# team_flag.net
KiCad netlist of a schematic drawn in EAGLE
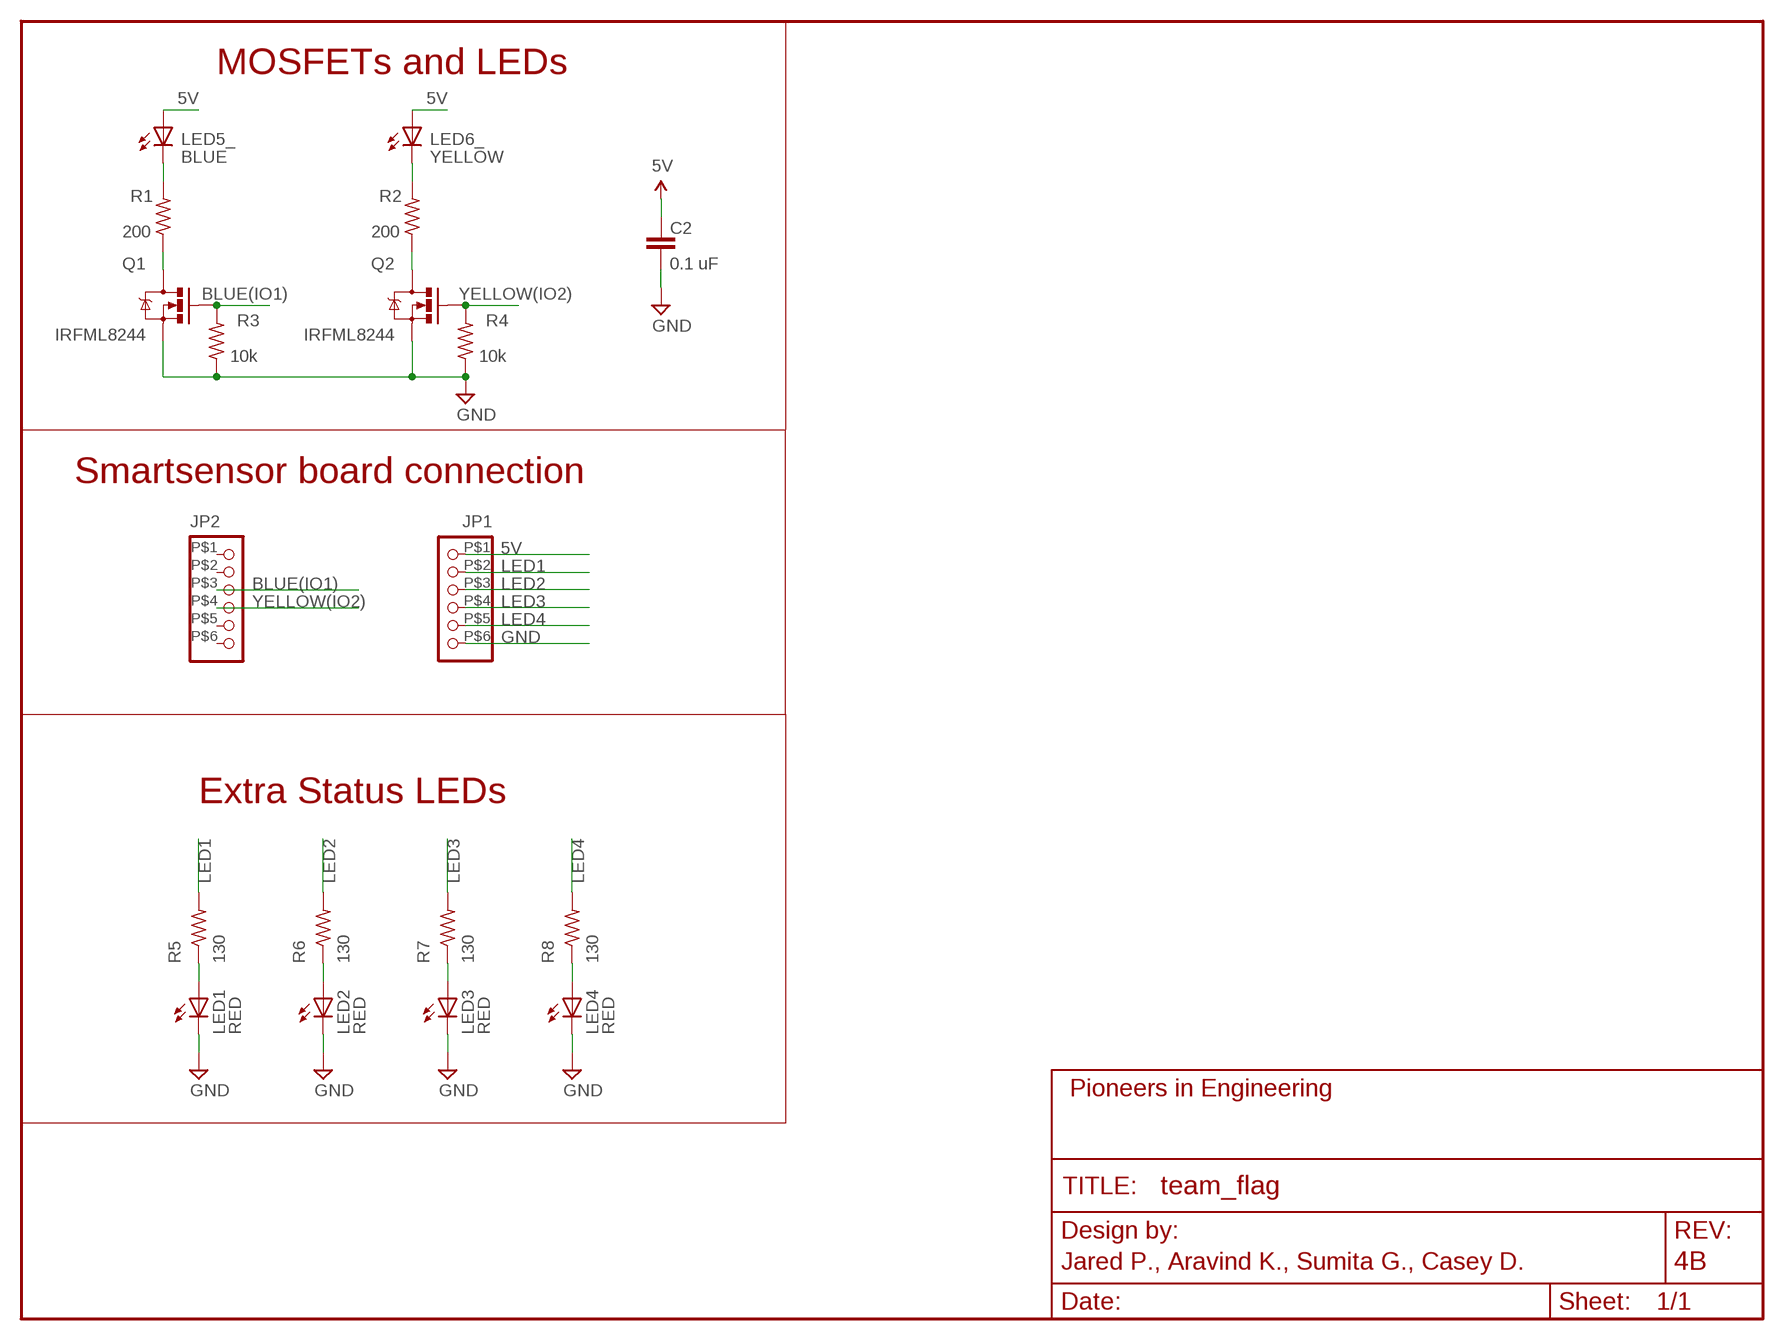
[diagram p0: schematic, sheet 1]

(export (version "E")
  (design (tool "Eeschema 10.0.6"))
  (components
    (comp (ref "C2")
      (value "0.1 uF")
      (footprint "eagle-import:0603-CAP")
      (libsource (lib "eagle-import") (part "CAP0603-CAP"))
    )
    (comp (ref "JP1")
      (value "PINHD-1X6SMD-C")
      (footprint "eagle-import:1X06-SMD-C")
      (libsource (lib "eagle-import") (part "PINHD-1X6SMD-C"))
    )
    (comp (ref "JP2")
      (value "PINHD-1X6SMD-C")
      (footprint "eagle-import:1X06-SMD-C")
      (libsource (lib "eagle-import") (part "PINHD-1X6SMD-C"))
    )
    (comp (ref "LED1")
      (value "RED")
      (footprint "eagle-import:LED-0805")
      (libsource (lib "eagle-import") (part "LED0805"))
    )
    (comp (ref "LED2")
      (value "RED")
      (footprint "eagle-import:LED-0805")
      (libsource (lib "eagle-import") (part "LED0805"))
    )
    (comp (ref "LED3")
      (value "RED")
      (footprint "eagle-import:LED-0805")
      (libsource (lib "eagle-import") (part "LED0805"))
    )
    (comp (ref "LED4")
      (value "RED")
      (footprint "eagle-import:LED-0805")
      (libsource (lib "eagle-import") (part "LED0805"))
    )
    (comp (ref "LED5_")
      (value "BLUE")
      (footprint "eagle-import:LED5MM-NOFLAT")
      (libsource (lib "eagle-import") (part "LEDLED5MM-NOFLAT"))
    )
    (comp (ref "LED6_")
      (value "YELLOW")
      (footprint "eagle-import:LED5MM-NOFLAT")
      (libsource (lib "eagle-import") (part "LEDLED5MM-NOFLAT"))
    )
    (comp (ref "Q1")
      (value "IRFML8244")
      (footprint "eagle-import:SOT23-3")
      (libsource (lib "eagle-import") (part "MOSFET-NCHANNELSMD"))
    )
    (comp (ref "Q2")
      (value "IRFML8244")
      (footprint "eagle-import:SOT23-3")
      (libsource (lib "eagle-import") (part "MOSFET-NCHANNELSMD"))
    )
    (comp (ref "R1")
      (value "200")
      (footprint "eagle-import:R0603")
      (libsource (lib "eagle-import") (part "R-US_R0603"))
    )
    (comp (ref "R2")
      (value "200")
      (footprint "eagle-import:R0603")
      (libsource (lib "eagle-import") (part "R-US_R0603"))
    )
    (comp (ref "R3")
      (value "10k")
      (footprint "eagle-import:R0603")
      (libsource (lib "eagle-import") (part "R-US_R0603"))
    )
    (comp (ref "R4")
      (value "10k")
      (footprint "eagle-import:R0603")
      (libsource (lib "eagle-import") (part "R-US_R0603"))
    )
    (comp (ref "R5")
      (value "130")
      (footprint "eagle-import:R0603")
      (libsource (lib "eagle-import") (part "R-US_R0603"))
    )
    (comp (ref "R6")
      (value "130")
      (footprint "eagle-import:R0603")
      (libsource (lib "eagle-import") (part "R-US_R0603"))
    )
    (comp (ref "R7")
      (value "130")
      (footprint "eagle-import:R0603")
      (libsource (lib "eagle-import") (part "R-US_R0603"))
    )
    (comp (ref "R8")
      (value "130")
      (footprint "eagle-import:R0603")
      (libsource (lib "eagle-import") (part "R-US_R0603"))
    )
  )
  (nets
    (net (code "1") (name "/BLUE(IO1)") (class "Default")
      (node (ref "JP2") (pin "P$3") (pinfunction "3_P$3") (pintype "passive"))
      (node (ref "Q1") (pin "1") (pinfunction "G_1") (pintype "passive"))
      (node (ref "R3") (pin "2") (pinfunction "2_2") (pintype "passive"))
    )
    (net (code "2") (name "/LED1") (class "Default")
      (node (ref "JP1") (pin "P$2") (pinfunction "2_P$2") (pintype "passive"))
      (node (ref "R5") (pin "2") (pinfunction "2_2") (pintype "passive"))
    )
    (net (code "3") (name "/LED2") (class "Default")
      (node (ref "JP1") (pin "P$3") (pinfunction "3_P$3") (pintype "passive"))
      (node (ref "R6") (pin "2") (pinfunction "2_2") (pintype "passive"))
    )
    (net (code "4") (name "/LED3") (class "Default")
      (node (ref "JP1") (pin "P$4") (pinfunction "4_P$4") (pintype "passive"))
      (node (ref "R7") (pin "2") (pinfunction "2_2") (pintype "passive"))
    )
    (net (code "5") (name "/LED4") (class "Default")
      (node (ref "JP1") (pin "P$5") (pinfunction "5_P$5") (pintype "passive"))
      (node (ref "R8") (pin "2") (pinfunction "2_2") (pintype "passive"))
    )
    (net (code "6") (name "/YELLOW(IO2)") (class "Default")
      (node (ref "JP2") (pin "P$4") (pinfunction "4_P$4") (pintype "passive"))
      (node (ref "Q2") (pin "1") (pinfunction "G_1") (pintype "passive"))
      (node (ref "R4") (pin "2") (pinfunction "2_2") (pintype "passive"))
    )
    (net (code "7") (name "5V") (class "Default")
      (node (ref "C2") (pin "1") (pinfunction "1_1") (pintype "passive"))
      (node (ref "JP1") (pin "P$1") (pinfunction "1_P$1") (pintype "passive"))
      (node (ref "LED5_") (pin "A") (pinfunction "A_A") (pintype "passive"))
      (node (ref "LED6_") (pin "A") (pinfunction "A_A") (pintype "passive"))
    )
    (net (code "8") (name "GND") (class "Default")
      (node (ref "C2") (pin "2") (pinfunction "2_2") (pintype "passive"))
      (node (ref "JP1") (pin "P$6") (pinfunction "6_P$6") (pintype "passive"))
      (node (ref "LED1") (pin "C") (pinfunction "C_C") (pintype "passive"))
      (node (ref "LED2") (pin "C") (pinfunction "C_C") (pintype "passive"))
      (node (ref "LED3") (pin "C") (pinfunction "C_C") (pintype "passive"))
      (node (ref "LED4") (pin "C") (pinfunction "C_C") (pintype "passive"))
      (node (ref "Q1") (pin "2") (pinfunction "S_2") (pintype "passive"))
      (node (ref "Q2") (pin "2") (pinfunction "S_2") (pintype "passive"))
      (node (ref "R3") (pin "1") (pinfunction "1_1") (pintype "passive"))
      (node (ref "R4") (pin "1") (pinfunction "1_1") (pintype "passive"))
    )
    (net (code "9") (name "Net-(LED1-PadA)") (class "Default")
      (node (ref "LED1") (pin "A") (pinfunction "A_A") (pintype "passive"))
      (node (ref "R5") (pin "1") (pinfunction "1_1") (pintype "passive"))
    )
    (net (code "10") (name "Net-(LED2-PadA)") (class "Default")
      (node (ref "LED2") (pin "A") (pinfunction "A_A") (pintype "passive"))
      (node (ref "R6") (pin "1") (pinfunction "1_1") (pintype "passive"))
    )
    (net (code "11") (name "Net-(LED3-PadA)") (class "Default")
      (node (ref "LED3") (pin "A") (pinfunction "A_A") (pintype "passive"))
      (node (ref "R7") (pin "1") (pinfunction "1_1") (pintype "passive"))
    )
    (net (code "12") (name "Net-(LED4-PadA)") (class "Default")
      (node (ref "LED4") (pin "A") (pinfunction "A_A") (pintype "passive"))
      (node (ref "R8") (pin "1") (pinfunction "1_1") (pintype "passive"))
    )
    (net (code "13") (name "Net-(LED5_-C)") (class "Default")
      (node (ref "LED5_") (pin "K") (pinfunction "C_K") (pintype "passive"))
      (node (ref "R1") (pin "2") (pinfunction "2_2") (pintype "passive"))
    )
    (net (code "14") (name "Net-(LED6_-C)") (class "Default")
      (node (ref "LED6_") (pin "K") (pinfunction "C_K") (pintype "passive"))
      (node (ref "R2") (pin "2") (pinfunction "2_2") (pintype "passive"))
    )
    (net (code "15") (name "Net-(Q1-D)") (class "Default")
      (node (ref "Q1") (pin "3") (pinfunction "D_3") (pintype "passive"))
      (node (ref "R1") (pin "1") (pinfunction "1_1") (pintype "passive"))
    )
    (net (code "16") (name "Net-(Q2-D)") (class "Default")
      (node (ref "Q2") (pin "3") (pinfunction "D_3") (pintype "passive"))
      (node (ref "R2") (pin "1") (pinfunction "1_1") (pintype "passive"))
    )
    (net (code "17") (name "unconnected-(JP2-1-PadP$1)") (class "Default")
      (node (ref "JP2") (pin "P$1") (pinfunction "1_P$1") (pintype "passive"))
    )
    (net (code "18") (name "unconnected-(JP2-2-PadP$2)") (class "Default")
      (node (ref "JP2") (pin "P$2") (pinfunction "2_P$2") (pintype "passive"))
    )
    (net (code "19") (name "unconnected-(JP2-5-PadP$5)") (class "Default")
      (node (ref "JP2") (pin "P$5") (pinfunction "5_P$5") (pintype "passive"))
    )
    (net (code "20") (name "unconnected-(JP2-6-PadP$6)") (class "Default")
      (node (ref "JP2") (pin "P$6") (pinfunction "6_P$6") (pintype "passive"))
    )
  )
)
